# main_board.net
KiCad netlist of a schematic drawn in EAGLE
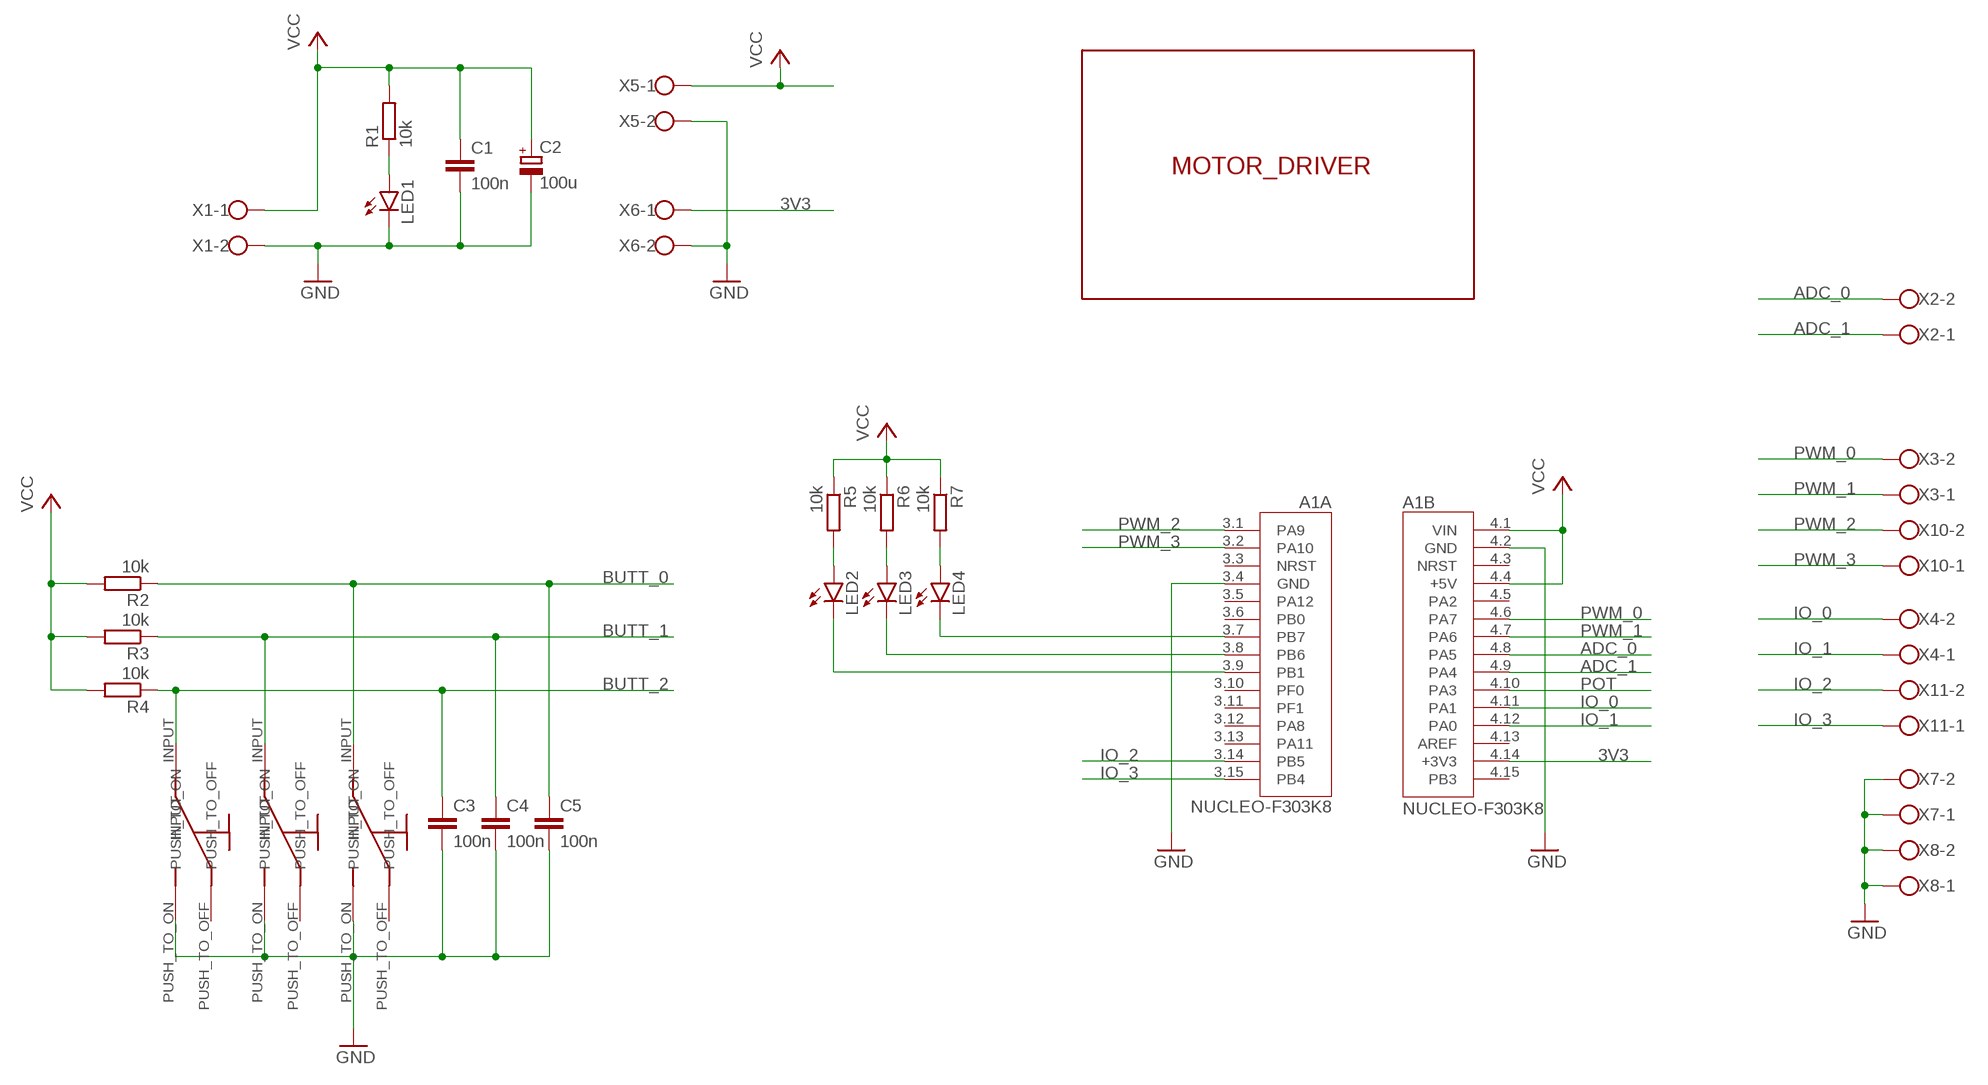
[diagram p0: schematic, sheet 1]

(export (version "E")
  (design (tool "Eeschema 10.0.6"))
  (components
    (comp (ref "A1")
      (value "NUCLEO-F303K8")
      (footprint "eagle-import:MODULE_NUCLEO-F303K8")
      (fields (field (name "MF") "STMicroelectronics"))
      (libsource (lib "eagle-import") (part "NUCLEO-F303K8"))
    )
    (comp (ref "C1")
      (value "100n")
      (footprint "eagle-import:C1206")
      (libsource (lib "eagle-import") (part "C-EUC1206"))
    )
    (comp (ref "C2")
      (value "100u")
      (footprint "eagle-import:150CLZ-1010")
      (libsource (lib "eagle-import") (part "CPOL-EU150CLZ-1010"))
    )
    (comp (ref "C3")
      (value "100n")
      (footprint "eagle-import:C1206")
      (libsource (lib "eagle-import") (part "C-EUC1206"))
    )
    (comp (ref "C4")
      (value "100n")
      (footprint "eagle-import:C1206")
      (libsource (lib "eagle-import") (part "C-EUC1206"))
    )
    (comp (ref "C5")
      (value "100n")
      (footprint "eagle-import:C1206")
      (libsource (lib "eagle-import") (part "C-EUC1206"))
    )
    (comp (ref "LED1")
      (value "LEDSMT1206")
      (footprint "eagle-import:1206")
      (libsource (lib "eagle-import") (part "LEDSMT1206"))
    )
    (comp (ref "LED2")
      (value "LEDCHIPLED_1206")
      (footprint "eagle-import:CHIPLED_1206")
      (libsource (lib "eagle-import") (part "LEDCHIPLED_1206"))
    )
    (comp (ref "LED3")
      (value "LEDCHIPLED_1206")
      (footprint "eagle-import:CHIPLED_1206")
      (libsource (lib "eagle-import") (part "LEDCHIPLED_1206"))
    )
    (comp (ref "LED4")
      (value "LEDCHIPLED_1206")
      (footprint "eagle-import:CHIPLED_1206")
      (libsource (lib "eagle-import") (part "LEDCHIPLED_1206"))
    )
    (comp (ref "R1")
      (value "10k")
      (footprint "eagle-import:R1206")
      (libsource (lib "eagle-import") (part "R-EU_R1206"))
    )
    (comp (ref "R2")
      (value "10k")
      (footprint "eagle-import:R1206")
      (libsource (lib "eagle-import") (part "R-EU_R1206"))
    )
    (comp (ref "R3")
      (value "10k")
      (footprint "eagle-import:R1206")
      (libsource (lib "eagle-import") (part "R-EU_R1206"))
    )
    (comp (ref "R4")
      (value "10k")
      (footprint "eagle-import:R1206")
      (libsource (lib "eagle-import") (part "R-EU_R1206"))
    )
    (comp (ref "R5")
      (value "10k")
      (footprint "eagle-import:R1206")
      (libsource (lib "eagle-import") (part "R-EU_R1206"))
    )
    (comp (ref "R6")
      (value "10k")
      (footprint "eagle-import:R1206")
      (libsource (lib "eagle-import") (part "R-EU_R1206"))
    )
    (comp (ref "R7")
      (value "10k")
      (footprint "eagle-import:R1206")
      (libsource (lib "eagle-import") (part "R-EU_R1206"))
    )
    (comp (ref "U$2")
      (value "BUTTON")
      (footprint "eagle-import:BUTTON")
      (libsource (lib "eagle-import") (part "BUTTON"))
    )
    (comp (ref "U$3")
      (value "BUTTON")
      (footprint "eagle-import:BUTTON")
      (libsource (lib "eagle-import") (part "BUTTON"))
    )
    (comp (ref "U$4")
      (value "BUTTON")
      (footprint "eagle-import:BUTTON")
      (libsource (lib "eagle-import") (part "BUTTON"))
    )
    (comp (ref "U$5")
      (value "MOTOR_DRIVER")
      (footprint "eagle-import:MOTOR_DRIVER")
      (libsource (lib "eagle-import") (part "MOTOR_DRIVER"))
    )
    (comp (ref "X1")
      (value "W237-102")
      (footprint "eagle-import:W237-102")
      (fields (field (name "MPN") "237-102"))
      (libsource (lib "eagle-import") (part "W237-102"))
    )
    (comp (ref "X2")
      (value "W237-102")
      (footprint "eagle-import:W237-102")
      (fields (field (name "MPN") "237-102"))
      (libsource (lib "eagle-import") (part "W237-102"))
    )
    (comp (ref "X3")
      (value "W237-102")
      (footprint "eagle-import:W237-102")
      (fields (field (name "MPN") "237-102"))
      (libsource (lib "eagle-import") (part "W237-102"))
    )
    (comp (ref "X4")
      (value "W237-102")
      (footprint "eagle-import:W237-102")
      (fields (field (name "MPN") "237-102"))
      (libsource (lib "eagle-import") (part "W237-102"))
    )
    (comp (ref "X5")
      (value "W237-102")
      (footprint "eagle-import:W237-102")
      (fields (field (name "MPN") "237-102"))
      (libsource (lib "eagle-import") (part "W237-102"))
    )
    (comp (ref "X6")
      (value "W237-102")
      (footprint "eagle-import:W237-102")
      (fields (field (name "MPN") "237-102"))
      (libsource (lib "eagle-import") (part "W237-102"))
    )
    (comp (ref "X7")
      (value "W237-102")
      (footprint "eagle-import:W237-102")
      (fields (field (name "MPN") "237-102"))
      (libsource (lib "eagle-import") (part "W237-102"))
    )
    (comp (ref "X8")
      (value "W237-102")
      (footprint "eagle-import:W237-102")
      (fields (field (name "MPN") "237-102"))
      (libsource (lib "eagle-import") (part "W237-102"))
    )
    (comp (ref "X10")
      (value "W237-102")
      (footprint "eagle-import:W237-102")
      (fields (field (name "MPN") "237-102"))
      (libsource (lib "eagle-import") (part "W237-102"))
    )
    (comp (ref "X11")
      (value "W237-102")
      (footprint "eagle-import:W237-102")
      (fields (field (name "MPN") "237-102"))
      (libsource (lib "eagle-import") (part "W237-102"))
    )
  )
  (nets
    (net (code "1") (name "/3V3") (class "Default")
      (node (ref "A1") (pin "4.14") (pinfunction "+3V3_4.14") (pintype "bidirectional"))
      (node (ref "X6") (pin "1") (pinfunction "KL_1") (pintype "passive"))
    )
    (net (code "2") (name "/ADC_0") (class "Default")
      (node (ref "A1") (pin "4.8") (pinfunction "PA5_4.8") (pintype "bidirectional"))
      (node (ref "X2") (pin "2") (pinfunction "KL_2") (pintype "passive"))
    )
    (net (code "3") (name "/ADC_1") (class "Default")
      (node (ref "A1") (pin "4.9") (pinfunction "PA4_4.9") (pintype "bidirectional"))
      (node (ref "X2") (pin "1") (pinfunction "KL_1") (pintype "passive"))
    )
    (net (code "4") (name "/BUTT_0") (class "Default")
      (node (ref "C5") (pin "1") (pinfunction "1_1") (pintype "passive"))
      (node (ref "R2") (pin "1") (pinfunction "1_1") (pintype "passive"))
      (node (ref "U$4") (pin "INPUT") (pinfunction "INPUT_INPUT") (pintype "bidirectional"))
    )
    (net (code "5") (name "/BUTT_1") (class "Default")
      (node (ref "C4") (pin "1") (pinfunction "1_1") (pintype "passive"))
      (node (ref "R3") (pin "1") (pinfunction "1_1") (pintype "passive"))
      (node (ref "U$2") (pin "INPUT") (pinfunction "INPUT_INPUT") (pintype "bidirectional"))
    )
    (net (code "6") (name "/BUTT_2") (class "Default")
      (node (ref "C3") (pin "1") (pinfunction "1_1") (pintype "passive"))
      (node (ref "R4") (pin "1") (pinfunction "1_1") (pintype "passive"))
      (node (ref "U$3") (pin "INPUT") (pinfunction "INPUT_INPUT") (pintype "bidirectional"))
    )
    (net (code "7") (name "/IO_0") (class "Default")
      (node (ref "A1") (pin "4.11") (pinfunction "PA1_4.11") (pintype "bidirectional"))
      (node (ref "X4") (pin "2") (pinfunction "KL_2") (pintype "passive"))
    )
    (net (code "8") (name "/IO_1") (class "Default")
      (node (ref "A1") (pin "4.12") (pinfunction "PA0_4.12") (pintype "bidirectional"))
      (node (ref "X4") (pin "1") (pinfunction "KL_1") (pintype "passive"))
    )
    (net (code "9") (name "/IO_2") (class "Default")
      (node (ref "A1") (pin "3.14") (pinfunction "PB5_3.14") (pintype "bidirectional"))
      (node (ref "X11") (pin "2") (pinfunction "KL_2") (pintype "passive"))
    )
    (net (code "10") (name "/IO_3") (class "Default")
      (node (ref "A1") (pin "3.15") (pinfunction "PB4_3.15") (pintype "bidirectional"))
      (node (ref "X11") (pin "1") (pinfunction "KL_1") (pintype "passive"))
    )
    (net (code "11") (name "/POT") (class "Default")
      (node (ref "A1") (pin "4.10") (pinfunction "PA3_4.10") (pintype "bidirectional"))
    )
    (net (code "12") (name "/PWM_0") (class "Default")
      (node (ref "A1") (pin "4.6") (pinfunction "PA7_4.6") (pintype "bidirectional"))
      (node (ref "X3") (pin "2") (pinfunction "KL_2") (pintype "passive"))
    )
    (net (code "13") (name "/PWM_1") (class "Default")
      (node (ref "A1") (pin "4.7") (pinfunction "PA6_4.7") (pintype "bidirectional"))
      (node (ref "X3") (pin "1") (pinfunction "KL_1") (pintype "passive"))
    )
    (net (code "14") (name "/PWM_2") (class "Default")
      (node (ref "A1") (pin "3.1") (pinfunction "PA9_3.1") (pintype "bidirectional"))
      (node (ref "X10") (pin "2") (pinfunction "KL_2") (pintype "passive"))
    )
    (net (code "15") (name "/PWM_3") (class "Default")
      (node (ref "A1") (pin "3.2") (pinfunction "PA10_3.2") (pintype "bidirectional"))
      (node (ref "X10") (pin "1") (pinfunction "KL_1") (pintype "passive"))
    )
    (net (code "16") (name "GND") (class "Default")
      (node (ref "A1") (pin "3.4") (pinfunction "GND_3.4") (pintype "bidirectional"))
      (node (ref "A1") (pin "4.2") (pinfunction "GND_4.2") (pintype "bidirectional"))
      (node (ref "C1") (pin "2") (pinfunction "2_2") (pintype "passive"))
      (node (ref "C2") (pin "-") (pinfunction "-_-") (pintype "passive"))
      (node (ref "C3") (pin "2") (pinfunction "2_2") (pintype "passive"))
      (node (ref "C4") (pin "2") (pinfunction "2_2") (pintype "passive"))
      (node (ref "C5") (pin "2") (pinfunction "2_2") (pintype "passive"))
      (node (ref "LED1") (pin "C") (pinfunction "C_C") (pintype "passive"))
      (node (ref "U$2") (pin "PUSH_TO_ON") (pinfunction "PUSH_TO_ON_PUSH_TO_ON") (pintype "bidirectional"))
      (node (ref "U$3") (pin "PUSH_TO_ON") (pinfunction "PUSH_TO_ON_PUSH_TO_ON") (pintype "bidirectional"))
      (node (ref "U$4") (pin "PUSH_TO_ON") (pinfunction "PUSH_TO_ON_PUSH_TO_ON") (pintype "bidirectional"))
      (node (ref "X1") (pin "2") (pinfunction "KL_2") (pintype "passive"))
      (node (ref "X5") (pin "2") (pinfunction "KL_2") (pintype "passive"))
      (node (ref "X6") (pin "2") (pinfunction "KL_2") (pintype "passive"))
      (node (ref "X7") (pin "1") (pinfunction "KL_1") (pintype "passive"))
      (node (ref "X7") (pin "2") (pinfunction "KL_2") (pintype "passive"))
      (node (ref "X8") (pin "1") (pinfunction "KL_1") (pintype "passive"))
      (node (ref "X8") (pin "2") (pinfunction "KL_2") (pintype "passive"))
    )
    (net (code "17") (name "Net-(A1A-PB1)") (class "Default")
      (node (ref "A1") (pin "3.9") (pinfunction "PB1_3.9") (pintype "bidirectional"))
      (node (ref "LED2") (pin "C") (pinfunction "C_C") (pintype "passive"))
    )
    (net (code "18") (name "Net-(A1A-PB6)") (class "Default")
      (node (ref "A1") (pin "3.8") (pinfunction "PB6_3.8") (pintype "bidirectional"))
      (node (ref "LED3") (pin "C") (pinfunction "C_C") (pintype "passive"))
    )
    (net (code "19") (name "Net-(A1A-PB7)") (class "Default")
      (node (ref "A1") (pin "3.7") (pinfunction "PB7_3.7") (pintype "bidirectional"))
      (node (ref "LED4") (pin "C") (pinfunction "C_C") (pintype "passive"))
    )
    (net (code "20") (name "Net-(LED1-PadA)") (class "Default")
      (node (ref "LED1") (pin "A") (pinfunction "A_A") (pintype "passive"))
      (node (ref "R1") (pin "1") (pinfunction "1_1") (pintype "passive"))
    )
    (net (code "21") (name "Net-(LED2-PadA)") (class "Default")
      (node (ref "LED2") (pin "A") (pinfunction "A_A") (pintype "passive"))
      (node (ref "R5") (pin "2") (pinfunction "2_2") (pintype "passive"))
    )
    (net (code "22") (name "Net-(LED3-PadA)") (class "Default")
      (node (ref "LED3") (pin "A") (pinfunction "A_A") (pintype "passive"))
      (node (ref "R6") (pin "2") (pinfunction "2_2") (pintype "passive"))
    )
    (net (code "23") (name "Net-(LED4-PadA)") (class "Default")
      (node (ref "LED4") (pin "A") (pinfunction "A_A") (pintype "passive"))
      (node (ref "R7") (pin "2") (pinfunction "2_2") (pintype "passive"))
    )
    (net (code "24") (name "VCC") (class "Default")
      (node (ref "A1") (pin "4.1") (pinfunction "VIN_4.1") (pintype "bidirectional"))
      (node (ref "A1") (pin "4.4") (pinfunction "+5V_4.4") (pintype "bidirectional"))
      (node (ref "C1") (pin "1") (pinfunction "1_1") (pintype "passive"))
      (node (ref "C2") (pin "+") (pinfunction "+_+") (pintype "passive"))
      (node (ref "R1") (pin "2") (pinfunction "2_2") (pintype "passive"))
      (node (ref "R2") (pin "2") (pinfunction "2_2") (pintype "passive"))
      (node (ref "R3") (pin "2") (pinfunction "2_2") (pintype "passive"))
      (node (ref "R4") (pin "2") (pinfunction "2_2") (pintype "passive"))
      (node (ref "R5") (pin "1") (pinfunction "1_1") (pintype "passive"))
      (node (ref "R6") (pin "1") (pinfunction "1_1") (pintype "passive"))
      (node (ref "R7") (pin "1") (pinfunction "1_1") (pintype "passive"))
      (node (ref "X1") (pin "1") (pinfunction "KL_1") (pintype "passive"))
      (node (ref "X5") (pin "1") (pinfunction "KL_1") (pintype "passive"))
    )
    (net (code "25") (name "unconnected-(A1A-NRST-Pad3.3)") (class "Default")
      (node (ref "A1") (pin "3.3") (pinfunction "NRST_3.3") (pintype "bidirectional"))
    )
    (net (code "26") (name "unconnected-(A1A-PA8-Pad3.12)") (class "Default")
      (node (ref "A1") (pin "3.12") (pinfunction "PA8_3.12") (pintype "bidirectional"))
    )
    (net (code "27") (name "unconnected-(A1A-PA11-Pad3.13)") (class "Default")
      (node (ref "A1") (pin "3.13") (pinfunction "PA11_3.13") (pintype "bidirectional"))
    )
    (net (code "28") (name "unconnected-(A1A-PA12-Pad3.5)") (class "Default")
      (node (ref "A1") (pin "3.5") (pinfunction "PA12_3.5") (pintype "bidirectional"))
    )
    (net (code "29") (name "unconnected-(A1A-PB0-Pad3.6)") (class "Default")
      (node (ref "A1") (pin "3.6") (pinfunction "PB0_3.6") (pintype "bidirectional"))
    )
    (net (code "30") (name "unconnected-(A1A-PF0-Pad3.10)") (class "Default")
      (node (ref "A1") (pin "3.10") (pinfunction "PF0_3.10") (pintype "bidirectional"))
    )
    (net (code "31") (name "unconnected-(A1A-PF1-Pad3.11)") (class "Default")
      (node (ref "A1") (pin "3.11") (pinfunction "PF1_3.11") (pintype "bidirectional"))
    )
    (net (code "32") (name "unconnected-(A1B-AREF-Pad4.13)") (class "Default")
      (node (ref "A1") (pin "4.13") (pinfunction "AREF_4.13") (pintype "bidirectional"))
    )
    (net (code "33") (name "unconnected-(A1B-NRST-Pad4.3)") (class "Default")
      (node (ref "A1") (pin "4.3") (pinfunction "NRST_4.3") (pintype "bidirectional"))
    )
    (net (code "34") (name "unconnected-(A1B-PA2-Pad4.5)") (class "Default")
      (node (ref "A1") (pin "4.5") (pinfunction "PA2_4.5") (pintype "bidirectional"))
    )
    (net (code "35") (name "unconnected-(A1B-PB3-Pad4.15)") (class "Default")
      (node (ref "A1") (pin "4.15") (pinfunction "PB3_4.15") (pintype "bidirectional"))
    )
    (net (code "36") (name "unconnected-(U$2-PadPUSH_TO_OFF)") (class "Default")
      (node (ref "U$2") (pin "PUSH_TO_OFF") (pinfunction "PUSH_TO_OFF_PUSH_TO_OFF") (pintype "bidirectional"))
    )
    (net (code "37") (name "unconnected-(U$3-PadPUSH_TO_OFF)") (class "Default")
      (node (ref "U$3") (pin "PUSH_TO_OFF") (pinfunction "PUSH_TO_OFF_PUSH_TO_OFF") (pintype "bidirectional"))
    )
    (net (code "38") (name "unconnected-(U$4-PadPUSH_TO_OFF)") (class "Default")
      (node (ref "U$4") (pin "PUSH_TO_OFF") (pinfunction "PUSH_TO_OFF_PUSH_TO_OFF") (pintype "bidirectional"))
    )
  )
)
